# 05_-_CPU_-_HDMI_LVDS.net
KiCad netlist of a schematic drawn in Altium Designer
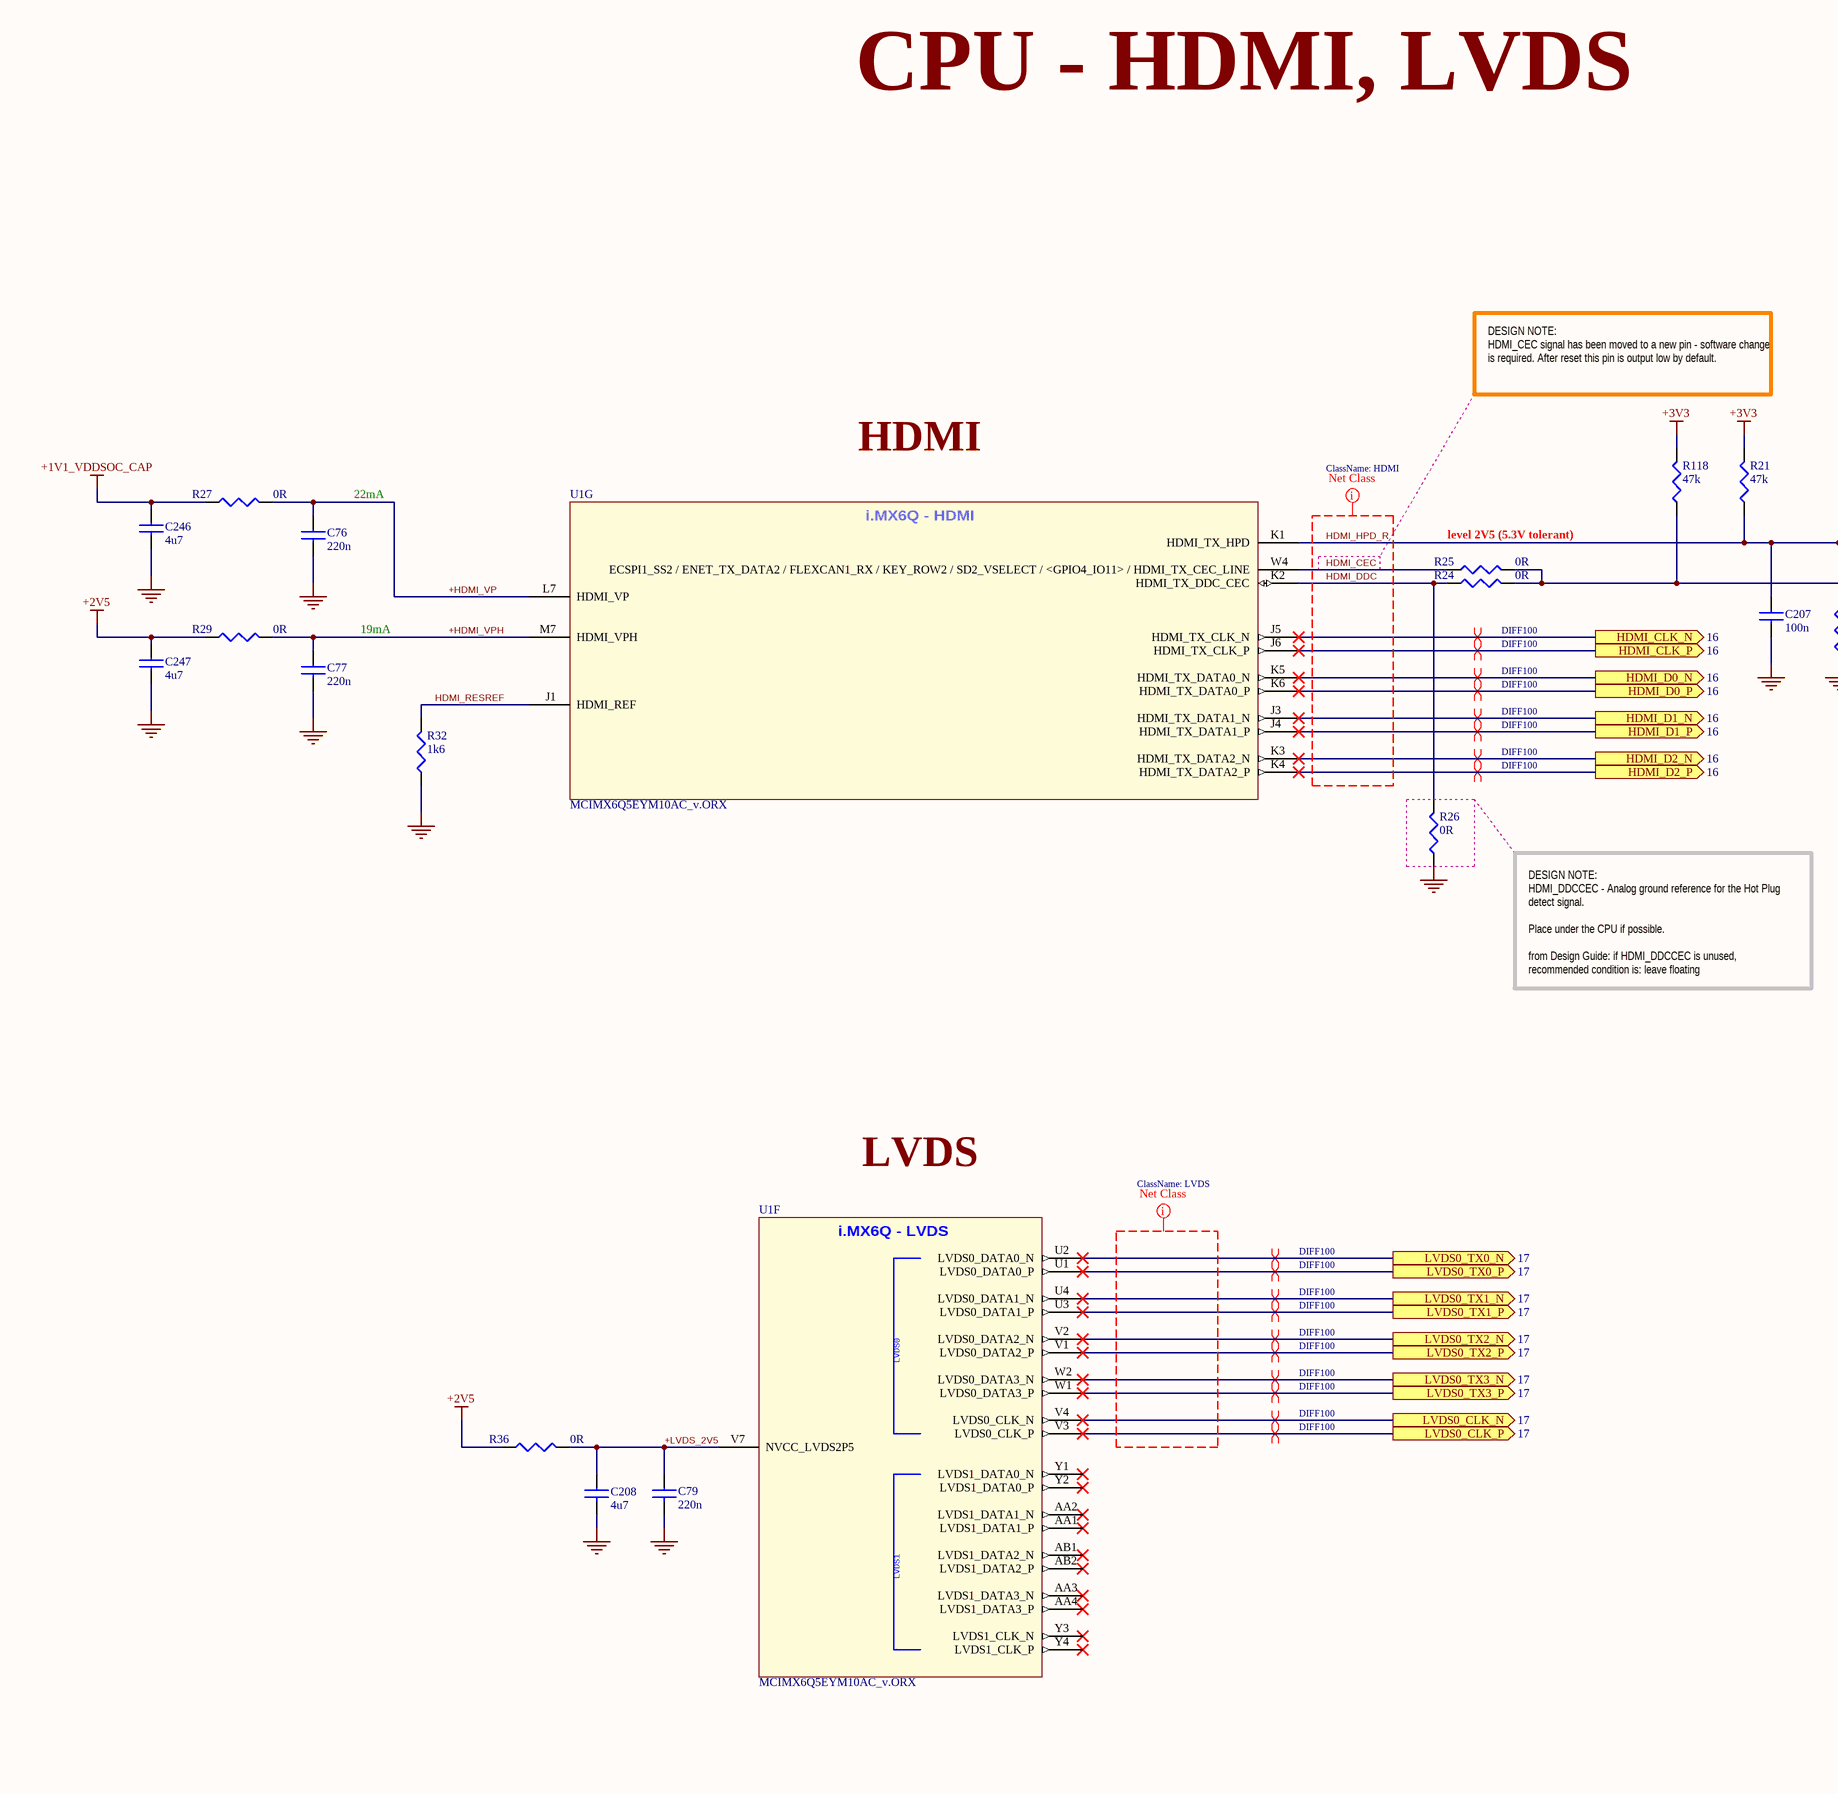
[diagram p0: [05] - CPU - HDMI, LVDS.SchDoc, left]
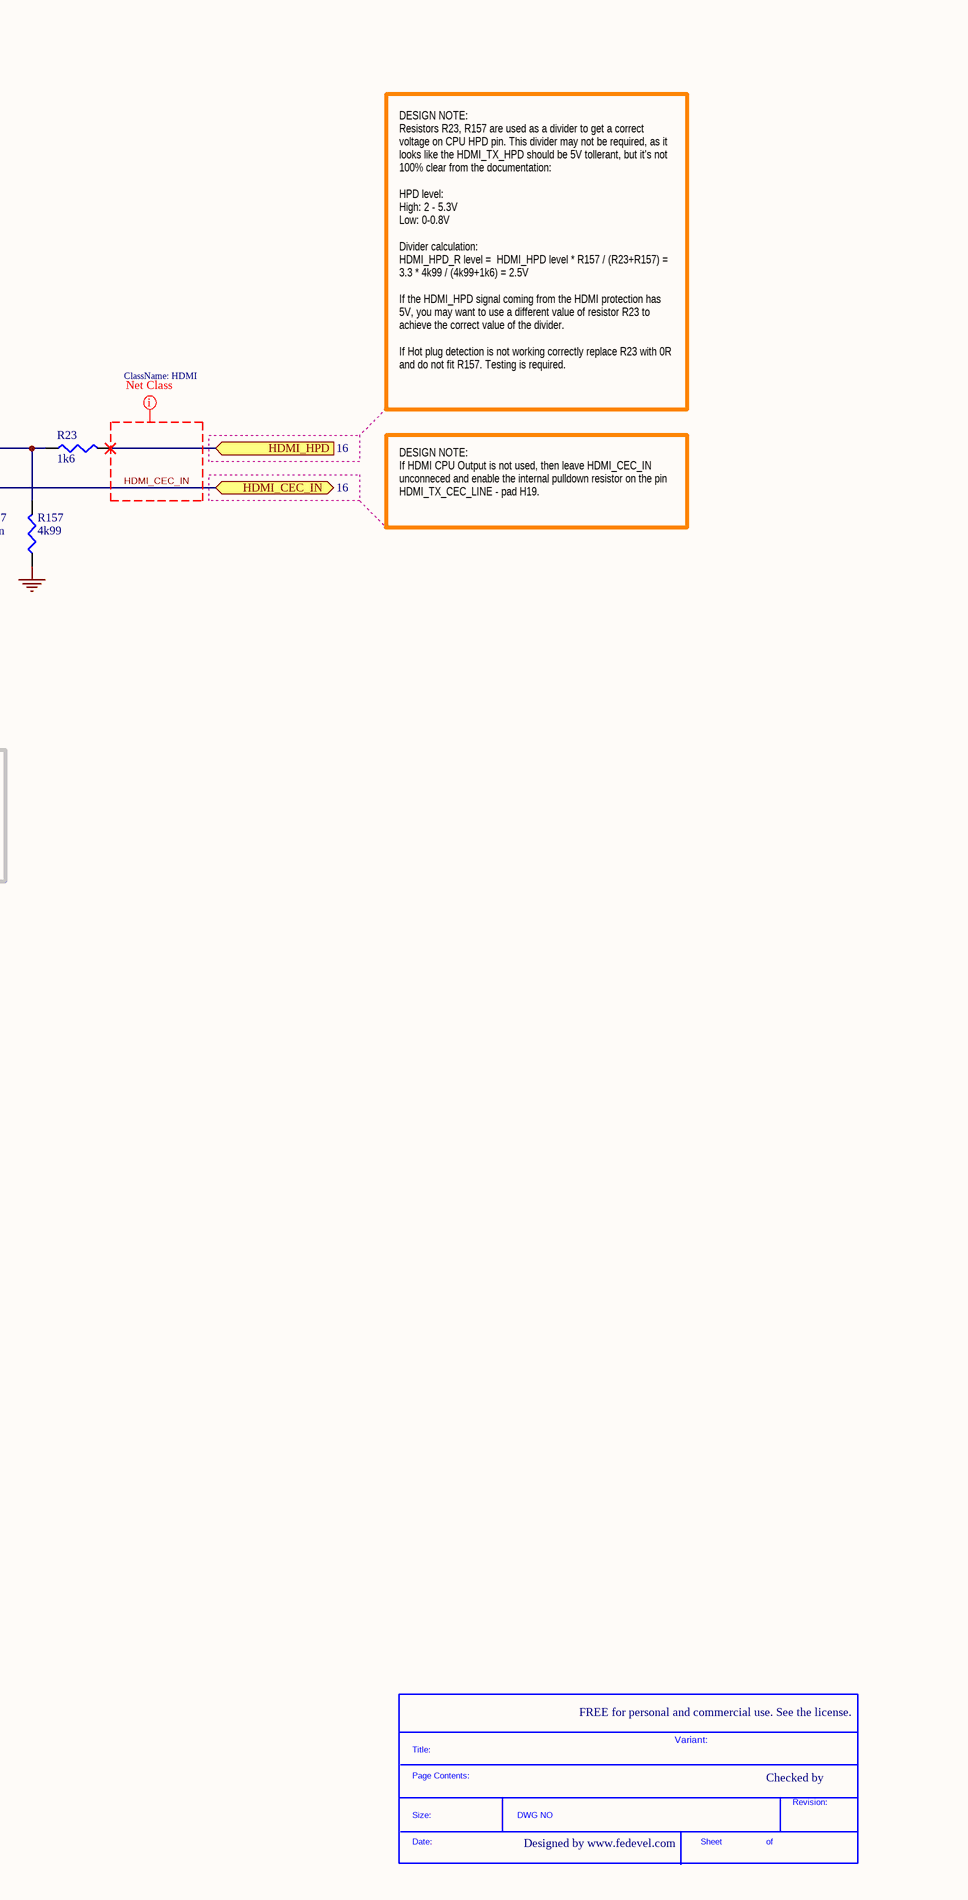
[diagram p1: [05] - CPU - HDMI, LVDS.SchDoc, right]

(export (version "E")
  (design (tool "Eeschema 10.0.6"))
  (components
    (comp (ref "C76")
      (value "220n")
      (footprint "C0201")
      (description "CAP CER 0.22UF 6.3V 20% X5R 0201")
      (fields
        (field (name "MANUFACTURER") "TDK Corporation")
        (field (name "MANUFACTURER PART NUMBER") "C0603X5R0J224M030BB")
        (field (name ".CHECKED PCB") "MM")
        (field (name ".CHECKED SCH") "MM")
        (field (name ".CREATOR") "MM")
      )
      (libsource (lib "Integrated_Library_FEDEVEL_0201") (part "C0603X5R0J224M030BB"))
    )
    (comp (ref "C77")
      (value "220n")
      (footprint "C0201")
      (description "CAP CER 0.22UF 6.3V 20% X5R 0201")
      (fields
        (field (name "MANUFACTURER") "TDK Corporation")
        (field (name "MANUFACTURER PART NUMBER") "C0603X5R0J224M030BB")
        (field (name ".CHECKED PCB") "MM")
        (field (name ".CHECKED SCH") "MM")
        (field (name ".CREATOR") "MM")
      )
      (libsource (lib "Integrated_Library_FEDEVEL_0201") (part "C0603X5R0J224M030BB"))
    )
    (comp (ref "C79")
      (value "220n")
      (footprint "C0201")
      (description "CAP CER 0.22UF 6.3V 20% X5R 0201")
      (fields
        (field (name "MANUFACTURER") "TDK Corporation")
        (field (name "MANUFACTURER PART NUMBER") "C0603X5R0J224M030BB")
        (field (name ".CHECKED PCB") "MM")
        (field (name ".CHECKED SCH") "MM")
        (field (name ".CREATOR") "MM")
      )
      (libsource (lib "Integrated_Library_FEDEVEL_0201") (part "C0603X5R0J224M030BB"))
    )
    (comp (ref "C207")
      (value "100n")
      (footprint "C0402")
      (description "CAP CER .10UF 50V X5R 10% 0402")
      (fields
        (field (name "MANUFACTURER") "TDK Corporation")
        (field (name "MANUFACTURER PART NUMBER") "C1005X5R1H104K")
      )
      (libsource (lib "Integrated_Library_FEDEVEL_APR_2015") (part "C1005X5R1H104K"))
    )
    (comp (ref "C208")
      (value "4u7")
      (footprint "C0402")
      (description "CAP CER 4.7UF 10V 20% X5R 0402")
      (fields
        (field (name "MANUFACTURER") "TDK Corporation")
        (field (name "MANUFACTURER PART NUMBER") "C1005X5R1A475M")
      )
      (libsource (lib "Integrated_Library_FEDEVEL_APR_2015") (part "C1005X5R1A475M"))
    )
    (comp (ref "C246")
      (value "4u7")
      (footprint "C0402")
      (description "CAP CER 4.7UF 10V 20% X5R 0402")
      (fields
        (field (name "MANUFACTURER") "TDK Corporation")
        (field (name "MANUFACTURER PART NUMBER") "C1005X5R1A475M")
      )
      (libsource (lib "Integrated_Library_FEDEVEL_APR_2015") (part "C1005X5R1A475M"))
    )
    (comp (ref "C247")
      (value "4u7")
      (footprint "C0402")
      (description "CAP CER 4.7UF 10V 20% X5R 0402")
      (fields
        (field (name "MANUFACTURER") "TDK Corporation")
        (field (name "MANUFACTURER PART NUMBER") "C1005X5R1A475M")
      )
      (libsource (lib "Integrated_Library_FEDEVEL_APR_2015") (part "C1005X5R1A475M"))
    )
    (comp (ref "R21")
      (value "47k")
      (footprint "R0402")
      (description "RES 47.0K OHM 1/16W 1% 0402 SMD")
      (fields
        (field (name "MANUFACTURER") "Yageo")
        (field (name "MANUFACTURER PART NUMBER") "RC0402FR-0747KL")
      )
      (libsource (lib "Integrated_Library_FEDEVEL_APR_2015") (part "RC0402FR-0747KL"))
    )
    (comp (ref "R23")
      (value "1k6")
      (footprint "R0402")
      (description "RES 1.6K OHM 1/10W 1% 0402 SMD")
      (fields
        (field (name "MANUFACTURER") "Panasonic Electronic Components")
        (field (name "MANUFACTURER PART NUMBER") "ERJ-2RKF1601X")
        (field (name ".CREATOR") "MM")
      )
      (libsource (lib "Integrated_Library_FEDEVEL_APR_2015") (part "ERJ-2RKF1601X"))
    )
    (comp (ref "R24")
      (value "0R")
      (footprint "R0402")
      (description "RES 0.0 OHM 1/16W 0402 SMD")
      (fields
        (field (name "MANUFACTURER") "Yageo")
        (field (name "MANUFACTURER PART NUMBER") "RC0402JR-070RL")
      )
      (libsource (lib "Integrated_Library_FEDEVEL_APR_2015") (part "RC0402JR-070RL"))
    )
    (comp (ref "R25")
      (value "0R")
      (footprint "R0402")
      (description "RES 0.0 OHM 1/16W 0402 SMD")
      (fields
        (field (name "MANUFACTURER") "Yageo")
        (field (name "MANUFACTURER PART NUMBER") "RC0402JR-070RL")
      )
      (libsource (lib "Integrated_Library_FEDEVEL_APR_2015") (part "RC0402JR-070RL"))
    )
    (comp (ref "R26")
      (value "0R")
      (footprint "R0402")
      (description "RES 0.0 OHM 1/16W 0402 SMD")
      (fields
        (field (name "MANUFACTURER") "Yageo")
        (field (name "MANUFACTURER PART NUMBER") "RC0402JR-070RL")
      )
      (libsource (lib "Integrated_Library_FEDEVEL_APR_2015") (part "RC0402JR-070RL"))
    )
    (comp (ref "R27")
      (value "0R")
      (footprint "R0402")
      (description "RES 0.0 OHM 1/16W 0402 SMD")
      (fields
        (field (name "MANUFACTURER") "Yageo")
        (field (name "MANUFACTURER PART NUMBER") "RC0402JR-070RL")
      )
      (libsource (lib "Integrated_Library_FEDEVEL_APR_2015") (part "RC0402JR-070RL"))
    )
    (comp (ref "R29")
      (value "0R")
      (footprint "R0402")
      (description "RES 0.0 OHM 1/16W 0402 SMD")
      (fields
        (field (name "MANUFACTURER") "Yageo")
        (field (name "MANUFACTURER PART NUMBER") "RC0402JR-070RL")
      )
      (libsource (lib "Integrated_Library_FEDEVEL_APR_2015") (part "RC0402JR-070RL"))
    )
    (comp (ref "R32")
      (value "1k6")
      (footprint "R0201")
      (description "RES 1.60K OHM 1/20W 1% 0201 SMD")
      (fields
        (field (name "MANUFACTURER") "Vishay Dale")
        (field (name "MANUFACTURER PART NUMBER") "CRCW02011K60FKED")
        (field (name ".CREATOR") "MM")
        (field (name ".CHECKED PCB") "MM")
        (field (name ".CHECKED SCH") "MM")
      )
      (libsource (lib "Integrated_Library_FEDEVEL_0201") (part "CRCW02011K60FKED"))
    )
    (comp (ref "R36")
      (value "0R")
      (footprint "R0402")
      (description "RES 0.0 OHM 1/16W 0402 SMD")
      (fields
        (field (name "MANUFACTURER") "Yageo")
        (field (name "MANUFACTURER PART NUMBER") "RC0402JR-070RL")
      )
      (libsource (lib "Integrated_Library_FEDEVEL_APR_2015") (part "RC0402JR-070RL"))
    )
    (comp (ref "R118")
      (value "47k")
      (footprint "R0402")
      (description "RES 47.0K OHM 1/16W 1% 0402 SMD")
      (fields
        (field (name "MANUFACTURER") "Yageo")
        (field (name "MANUFACTURER PART NUMBER") "RC0402FR-0747KL")
      )
      (libsource (lib "Integrated_Library_FEDEVEL_APR_2015") (part "RC0402FR-0747KL"))
    )
    (comp (ref "R157")
      (value "4k99")
      (footprint "R0402")
      (description "RES TF 4.99K OHM 1% 1/16W 0402")
      (fields
        (field (name "MANUFACTURER") "Stackpole Electronics Inc")
        (field (name "MANUFACTURER PART NUMBER") "RMCF0402FT4K99")
      )
      (libsource (lib "Integrated_Library_FEDEVEL_APR_2015") (part "RMCF0402FT4K99"))
    )
    (comp (ref "U1")
      (value "MCIMX6Q5EYM10AC_v.ORX")
      (footprint "PBGA624")
      (description "IC MCU 32BIT ARM QUAD 624FCBGA")
      (fields
        (field (name "MANUFACTURER") "Freescale Semiconductor")
        (field (name "MANUFACTURER PART NUMBER") "MCIMX6Q5EYM10AC")
        (field (name ".CREATOR") "MM")
        (field (name ".CHECKED PCB") "MM, checked by RF")
      )
      (libsource (lib "Integrated_Library_FEDEVEL_APR_2015") (part "MCIMX6Q5EYM10AC_v.ORX"))
    )
  )
  (nets
    (net (code "1") (name "+1V1_VDDSOC_CAP") (class "Default")
      (node (ref "C246") (pin "1") (pinfunction "1_1") (pintype "passive"))
      (node (ref "R27") (pin "1") (pinfunction "1_1") (pintype "passive"))
    )
    (net (code "2") (name "+2V5") (class "Default")
      (node (ref "C247") (pin "1") (pinfunction "1_1") (pintype "passive"))
      (node (ref "R29") (pin "1") (pinfunction "1_1") (pintype "passive"))
      (node (ref "R36") (pin "1") (pinfunction "1_1") (pintype "passive"))
    )
    (net (code "3") (name "+3V3") (class "Default")
      (node (ref "R118") (pin "2") (pinfunction "2_2") (pintype "passive"))
      (node (ref "R21") (pin "2") (pinfunction "2_2") (pintype "passive"))
    )
    (net (code "4") (name "/+HDMI_VP") (class "Default")
      (node (ref "C76") (pin "1") (pinfunction "1_1") (pintype "passive"))
      (node (ref "R27") (pin "2") (pinfunction "2_2") (pintype "passive"))
      (node (ref "U1") (pin "L7") (pinfunction "HDMI_VP_L7") (pintype "power_in"))
    )
    (net (code "5") (name "/+HDMI_VPH") (class "Default")
      (node (ref "C77") (pin "1") (pinfunction "1_1") (pintype "passive"))
      (node (ref "R29") (pin "2") (pinfunction "2_2") (pintype "passive"))
      (node (ref "U1") (pin "M7") (pinfunction "HDMI_VPH_M7") (pintype "power_in"))
    )
    (net (code "6") (name "/+LVDS_2V5") (class "Default")
      (node (ref "C208") (pin "1") (pinfunction "1_1") (pintype "passive"))
      (node (ref "C79") (pin "1") (pinfunction "1_1") (pintype "passive"))
      (node (ref "R36") (pin "2") (pinfunction "2_2") (pintype "passive"))
      (node (ref "U1") (pin "V7") (pinfunction "NVCC_LVDS2P5_V7") (pintype "power_in"))
    )
    (net (code "7") (name "/HDMI_CEC") (class "Default")
      (node (ref "R25") (pin "1") (pinfunction "1_1") (pintype "passive"))
      (node (ref "U1") (pin "W4") (pinfunction "ECSPI1_SS2_/_ENET_TX_DATA2_/_FLEXCAN1_RX_/_KEY_ROW2_/_SD2_VSELECT_/_<GPIO4_IO11>_/_HDMI_TX_CEC_LINE_W4") (pintype "passive"))
    )
    (net (code "8") (name "/HDMI_CEC_IN") (class "Default")
      (node (ref "R118") (pin "1") (pinfunction "1_1") (pintype "passive"))
      (node (ref "R24") (pin "2") (pinfunction "2_2") (pintype "passive"))
      (node (ref "R25") (pin "2") (pinfunction "2_2") (pintype "passive"))
    )
    (net (code "9") (name "/HDMI_CLK_N") (class "Default")
      (node (ref "U1") (pin "J5") (pinfunction "HDMI_TX_CLK_N_J5") (pintype "output+no_connect"))
    )
    (net (code "10") (name "/HDMI_CLK_P") (class "Default")
      (node (ref "U1") (pin "J6") (pinfunction "HDMI_TX_CLK_P_J6") (pintype "output+no_connect"))
    )
    (net (code "11") (name "/HDMI_D0_N") (class "Default")
      (node (ref "U1") (pin "K5") (pinfunction "HDMI_TX_DATA0_N_K5") (pintype "output+no_connect"))
    )
    (net (code "12") (name "/HDMI_D0_P") (class "Default")
      (node (ref "U1") (pin "K6") (pinfunction "HDMI_TX_DATA0_P_K6") (pintype "output+no_connect"))
    )
    (net (code "13") (name "/HDMI_D1_N") (class "Default")
      (node (ref "U1") (pin "J3") (pinfunction "HDMI_TX_DATA1_N_J3") (pintype "output+no_connect"))
    )
    (net (code "14") (name "/HDMI_D1_P") (class "Default")
      (node (ref "U1") (pin "J4") (pinfunction "HDMI_TX_DATA1_P_J4") (pintype "output+no_connect"))
    )
    (net (code "15") (name "/HDMI_D2_N") (class "Default")
      (node (ref "U1") (pin "K3") (pinfunction "HDMI_TX_DATA2_N_K3") (pintype "output+no_connect"))
    )
    (net (code "16") (name "/HDMI_D2_P") (class "Default")
      (node (ref "U1") (pin "K4") (pinfunction "HDMI_TX_DATA2_P_K4") (pintype "output+no_connect"))
    )
    (net (code "17") (name "/HDMI_DDC") (class "Default")
      (node (ref "R24") (pin "1") (pinfunction "1_1") (pintype "passive"))
      (node (ref "R26") (pin "2") (pinfunction "2_2") (pintype "passive"))
      (node (ref "U1") (pin "K2") (pinfunction "HDMI_TX_DDC_CEC_K2") (pintype "bidirectional"))
    )
    (net (code "18") (name "/HDMI_HPD") (class "Default")
      (node (ref "R23") (pin "2") (pinfunction "2_2") (pintype "passive+no_connect"))
    )
    (net (code "19") (name "/HDMI_HPD_R") (class "Default")
      (node (ref "C207") (pin "1") (pinfunction "1_1") (pintype "passive"))
      (node (ref "R157") (pin "2") (pinfunction "2_2") (pintype "passive"))
      (node (ref "R21") (pin "1") (pinfunction "1_1") (pintype "passive"))
      (node (ref "R23") (pin "1") (pinfunction "1_1") (pintype "passive"))
      (node (ref "U1") (pin "K1") (pinfunction "HDMI_TX_HPD_K1") (pintype "passive"))
    )
    (net (code "20") (name "/HDMI_RESREF") (class "Default")
      (node (ref "R32") (pin "2") (pinfunction "2_2") (pintype "passive"))
      (node (ref "U1") (pin "J1") (pinfunction "HDMI_REF_J1") (pintype "passive"))
    )
    (net (code "21") (name "/LVDS0_CLK_N") (class "Default")
      (node (ref "U1") (pin "V4") (pinfunction "LVDS0_CLK_N_V4") (pintype "output+no_connect"))
    )
    (net (code "22") (name "/LVDS0_CLK_P") (class "Default")
      (node (ref "U1") (pin "V3") (pinfunction "LVDS0_CLK_P_V3") (pintype "output+no_connect"))
    )
    (net (code "23") (name "/LVDS0_TX0_N") (class "Default")
      (node (ref "U1") (pin "U2") (pinfunction "LVDS0_DATA0_N_U2") (pintype "output+no_connect"))
    )
    (net (code "24") (name "/LVDS0_TX0_P") (class "Default")
      (node (ref "U1") (pin "U1") (pinfunction "LVDS0_DATA0_P_U1") (pintype "output+no_connect"))
    )
    (net (code "25") (name "/LVDS0_TX1_N") (class "Default")
      (node (ref "U1") (pin "U4") (pinfunction "LVDS0_DATA1_N_U4") (pintype "output+no_connect"))
    )
    (net (code "26") (name "/LVDS0_TX1_P") (class "Default")
      (node (ref "U1") (pin "U3") (pinfunction "LVDS0_DATA1_P_U3") (pintype "output+no_connect"))
    )
    (net (code "27") (name "/LVDS0_TX2_N") (class "Default")
      (node (ref "U1") (pin "V2") (pinfunction "LVDS0_DATA2_N_V2") (pintype "output+no_connect"))
    )
    (net (code "28") (name "/LVDS0_TX2_P") (class "Default")
      (node (ref "U1") (pin "V1") (pinfunction "LVDS0_DATA2_P_V1") (pintype "output+no_connect"))
    )
    (net (code "29") (name "/LVDS0_TX3_N") (class "Default")
      (node (ref "U1") (pin "W2") (pinfunction "LVDS0_DATA3_N_W2") (pintype "output+no_connect"))
    )
    (net (code "30") (name "/LVDS0_TX3_P") (class "Default")
      (node (ref "U1") (pin "W1") (pinfunction "LVDS0_DATA3_P_W1") (pintype "output+no_connect"))
    )
    (net (code "31") (name "GND") (class "Default")
      (node (ref "C207") (pin "2") (pinfunction "2_2") (pintype "passive"))
      (node (ref "C208") (pin "2") (pinfunction "2_2") (pintype "passive"))
      (node (ref "C246") (pin "2") (pinfunction "2_2") (pintype "passive"))
      (node (ref "C247") (pin "2") (pinfunction "2_2") (pintype "passive"))
      (node (ref "C76") (pin "2") (pinfunction "2_2") (pintype "passive"))
      (node (ref "C77") (pin "2") (pinfunction "2_2") (pintype "passive"))
      (node (ref "C79") (pin "2") (pinfunction "2_2") (pintype "passive"))
      (node (ref "R157") (pin "1") (pinfunction "1_1") (pintype "passive"))
      (node (ref "R26") (pin "1") (pinfunction "1_1") (pintype "passive"))
      (node (ref "R32") (pin "1") (pinfunction "1_1") (pintype "passive"))
    )
    (net (code "32") (name "unconnected-(U1F-LVDS1_CLK_N-PadY3)") (class "Default")
      (node (ref "U1") (pin "Y3") (pinfunction "LVDS1_CLK_N_Y3") (pintype "output+no_connect"))
    )
    (net (code "33") (name "unconnected-(U1F-LVDS1_CLK_P-PadY4)") (class "Default")
      (node (ref "U1") (pin "Y4") (pinfunction "LVDS1_CLK_P_Y4") (pintype "output+no_connect"))
    )
    (net (code "34") (name "unconnected-(U1F-LVDS1_DATA0_N-PadY1)") (class "Default")
      (node (ref "U1") (pin "Y1") (pinfunction "LVDS1_DATA0_N_Y1") (pintype "output+no_connect"))
    )
    (net (code "35") (name "unconnected-(U1F-LVDS1_DATA0_P-PadY2)") (class "Default")
      (node (ref "U1") (pin "Y2") (pinfunction "LVDS1_DATA0_P_Y2") (pintype "output+no_connect"))
    )
    (net (code "36") (name "unconnected-(U1F-LVDS1_DATA1_N-PadAA2)") (class "Default")
      (node (ref "U1") (pin "AA2") (pinfunction "LVDS1_DATA1_N_AA2") (pintype "output+no_connect"))
    )
    (net (code "37") (name "unconnected-(U1F-LVDS1_DATA1_P-PadAA1)") (class "Default")
      (node (ref "U1") (pin "AA1") (pinfunction "LVDS1_DATA1_P_AA1") (pintype "output+no_connect"))
    )
    (net (code "38") (name "unconnected-(U1F-LVDS1_DATA2_N-PadAB1)") (class "Default")
      (node (ref "U1") (pin "AB1") (pinfunction "LVDS1_DATA2_N_AB1") (pintype "output+no_connect"))
    )
    (net (code "39") (name "unconnected-(U1F-LVDS1_DATA2_P-PadAB2)") (class "Default")
      (node (ref "U1") (pin "AB2") (pinfunction "LVDS1_DATA2_P_AB2") (pintype "output+no_connect"))
    )
    (net (code "40") (name "unconnected-(U1F-LVDS1_DATA3_N-PadAA3)") (class "Default")
      (node (ref "U1") (pin "AA3") (pinfunction "LVDS1_DATA3_N_AA3") (pintype "output+no_connect"))
    )
    (net (code "41") (name "unconnected-(U1F-LVDS1_DATA3_P-PadAA4)") (class "Default")
      (node (ref "U1") (pin "AA4") (pinfunction "LVDS1_DATA3_P_AA4") (pintype "output+no_connect"))
    )
  )
)
